# mcu.net
KiCad netlist of a schematic drawn in Altium Designer
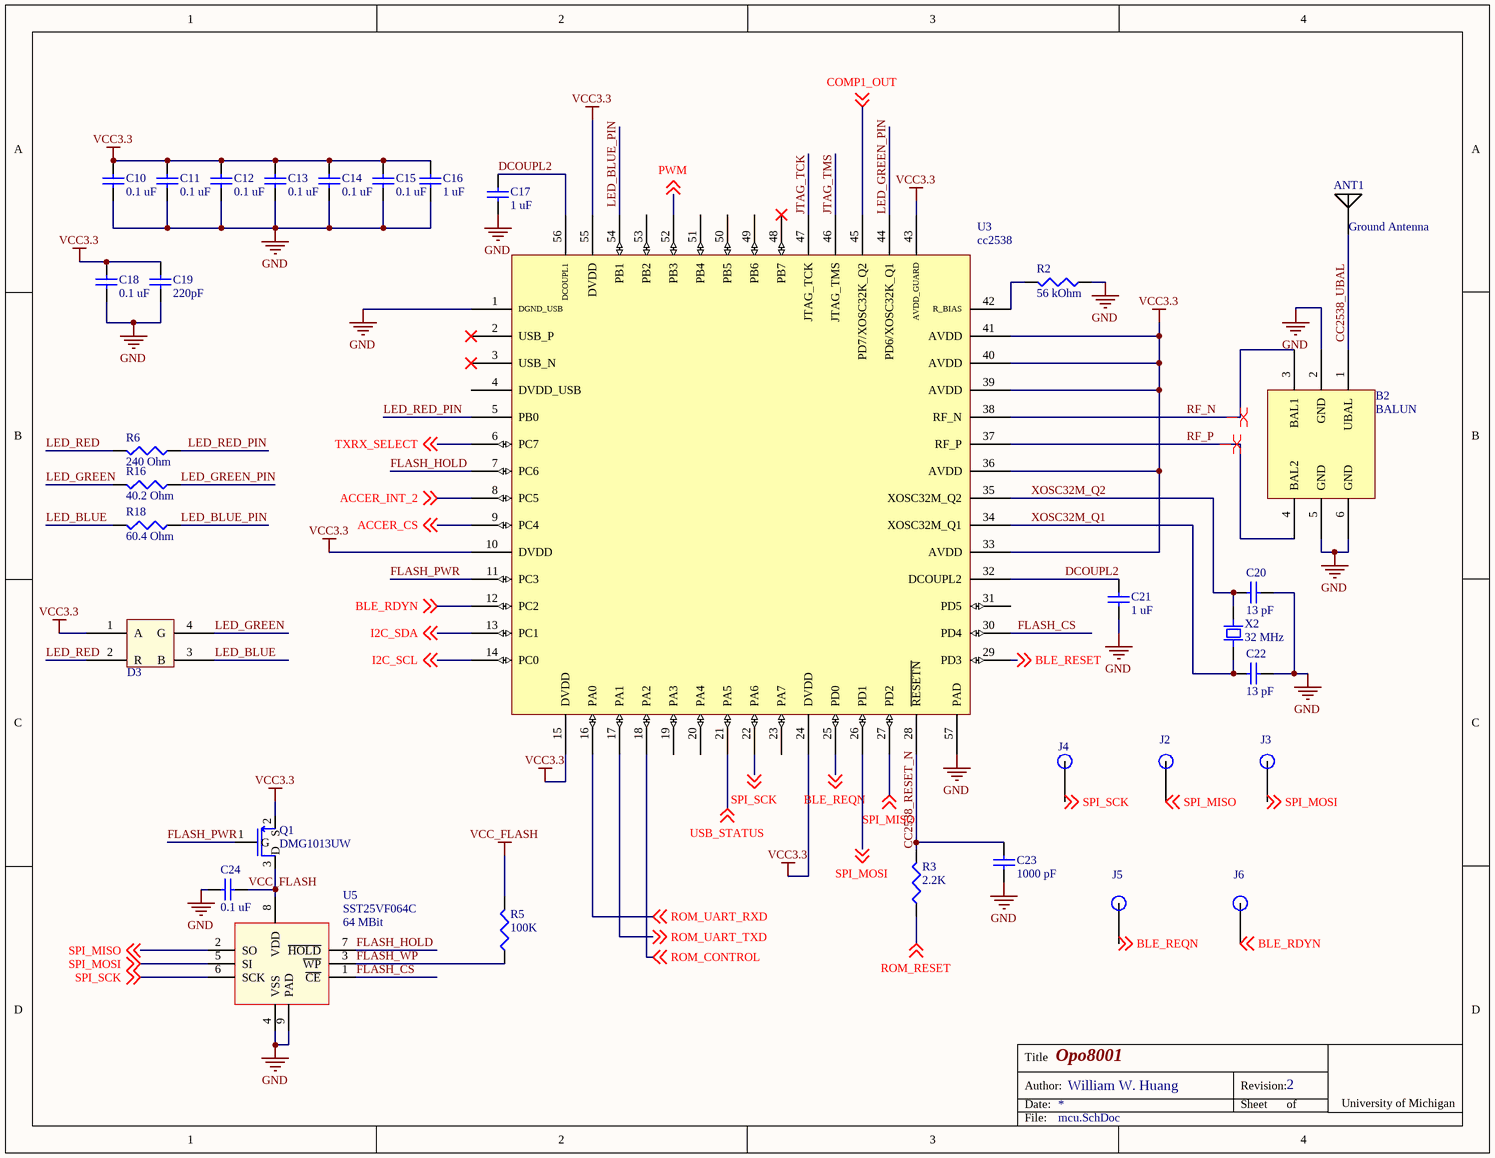
[diagram p0: mcu.SchDoc]

(export (version "E")
  (design (tool "Eeschema 10.0.6"))
  (components
    (comp (ref "ANT1")
      (value "Ground Antenna")
      (footprint "SMD Ground Antenna")
      (description "Molex 2.4 GHz SMD On-Ground Antenna")
      (libsource (lib "opo_general") (part "Molex Antenna"))
    )
    (comp (ref "B2")
      (value "BALUN")
      (footprint "2450BM15A0002")
      (description "Johanson CC253X Balun")
      (fields (field (name "MFR") "Johanson Technology") (field (name "MFR PART NUMBER") "2450BM15A0002"))
      (libsource (lib "opo_general") (part "cc2538_Balun"))
    )
    (comp (ref "C10")
      (value "0.1 uF")
      (footprint "0402")
      (description "Ceramic capacitor, 0.1u, 0402 package")
      (fields (field (name "TOLERANCE") "10%") (field (name "Comment") "Ceramic capacitor"))
      (libsource (lib "rlc") (part "C_0.1u_0402_ceramic"))
    )
    (comp (ref "C11")
      (value "0.1 uF")
      (footprint "0402")
      (description "Ceramic capacitor, 0.1u, 0402 package")
      (fields (field (name "TOLERANCE") "10%") (field (name "Comment") "Ceramic capacitor"))
      (libsource (lib "rlc") (part "C_0.1u_0402_ceramic"))
    )
    (comp (ref "C12")
      (value "0.1 uF")
      (footprint "0402")
      (description "Ceramic capacitor, 0.1u, 0402 package")
      (fields (field (name "TOLERANCE") "10%") (field (name "Comment") "Ceramic capacitor"))
      (libsource (lib "rlc") (part "C_0.1u_0402_ceramic"))
    )
    (comp (ref "C13")
      (value "0.1 uF")
      (footprint "0402")
      (description "Ceramic capacitor, 0.1u, 0402 package")
      (fields (field (name "TOLERANCE") "10%") (field (name "Comment") "Ceramic capacitor"))
      (libsource (lib "rlc") (part "C_0.1u_0402_ceramic"))
    )
    (comp (ref "C14")
      (value "0.1 uF")
      (footprint "0402")
      (description "Ceramic capacitor, 0.1u, 0402 package")
      (fields (field (name "TOLERANCE") "10%") (field (name "Comment") "Ceramic capacitor"))
      (libsource (lib "rlc") (part "C_0.1u_0402_ceramic"))
    )
    (comp (ref "C15")
      (value "0.1 uF")
      (footprint "0402")
      (description "Ceramic capacitor, 0.1u, 0402 package")
      (fields (field (name "TOLERANCE") "10%") (field (name "Comment") "Ceramic capacitor"))
      (libsource (lib "rlc") (part "C_0.1u_0402_ceramic"))
    )
    (comp (ref "C16")
      (value "1 uF")
      (footprint "0402")
      (description "Ceramic capacitor, 1 uF, 0402 package")
      (fields (field (name "TOLERANCE") "10%") (field (name "Comment") "Ceramic capacitor"))
      (libsource (lib "rlc") (part "C_1u_0402_ceramic"))
    )
    (comp (ref "C17")
      (value "1 uF")
      (footprint "0402")
      (description "Ceramic capacitor, 1 uF, 0402 package")
      (fields (field (name "TOLERANCE") "10%") (field (name "Comment") "Ceramic capacitor"))
      (libsource (lib "rlc") (part "C_1u_0402_ceramic"))
    )
    (comp (ref "C18")
      (value "0.1 uF")
      (footprint "0402")
      (description "Ceramic capacitor, 0.1u, 0402 package")
      (fields (field (name "TOLERANCE") "10%") (field (name "Comment") "Ceramic capacitor"))
      (libsource (lib "rlc") (part "C_0.1u_0402_ceramic"))
    )
    (comp (ref "C19")
      (value "220pF")
      (footprint "0402")
      (description "220pF 5% 50 V C0G NP0 0402 ceramic cap")
      (fields (field (name "MFR") "Murata") (field (name "MFR PART NUMBER") "GRM1555C1H221JA01D"))
      (libsource (lib "rlc") (part "C_220pf_0402_ceramic"))
    )
    (comp (ref "C20")
      (value "13 pF")
      (footprint "0402")
      (description "13pf, 50V, 2%, c0G, NP0, 0402, ceramic")
      (fields (field (name "MFR") "Murata") (field (name "MFR PART NUMBER") "GRM1555C1H130GA01D"))
      (libsource (lib "rlc") (part "C_13p_0402"))
    )
    (comp (ref "C21")
      (value "1 uF")
      (footprint "0402")
      (description "Ceramic capacitor, 1 uF, 0402 package")
      (fields (field (name "TOLERANCE") "10%") (field (name "Comment") "Ceramic capacitor"))
      (libsource (lib "rlc") (part "C_1u_0402_ceramic"))
    )
    (comp (ref "C22")
      (value "13 pF")
      (footprint "0402")
      (description "13pf, 50V, 2%, c0G, NP0, 0402, ceramic")
      (fields (field (name "MFR") "Murata") (field (name "MFR PART NUMBER") "GRM1555C1H130GA01D"))
      (libsource (lib "rlc") (part "C_13p_0402"))
    )
    (comp (ref "C23")
      (value "1000 pF")
      (footprint "0402")
      (description "Ceramic capacitor, 1000 pF, 0402 package")
      (fields (field (name "TOLERANCE") "10%") (field (name "Comment") "Ceramic capacitor"))
      (libsource (lib "rlc") (part "C_1000p_0402_ceramic"))
    )
    (comp (ref "C24")
      (value "0.1 uF")
      (footprint "0402")
      (description "Ceramic capacitor, 0.1u, 0402 package")
      (fields (field (name "TOLERANCE") "10%") (field (name "Comment") "Ceramic capacitor"))
      (libsource (lib "rlc") (part "C_0.1u_0402_ceramic"))
    )
    (comp (ref "D3")
      (value "Tri Color LED")
      (footprint "0404")
      (description "LED, RGB, 0404")
      (libsource (lib "rlc") (part "D_LED_RGB_0404"))
    )
    (comp (ref "J2")
      (value "RCU 0603 SMD Testpoint")
      (footprint "RCU_0603")
      (description "0603 SMD Testpoint")
      (libsource (lib "connectors") (part "Testpoint-0603"))
    )
    (comp (ref "J3")
      (value "RCU 0603 SMD Testpoint")
      (footprint "RCU_0603")
      (description "0603 SMD Testpoint")
      (libsource (lib "connectors") (part "Testpoint-0603"))
    )
    (comp (ref "J4")
      (value "RCU 0603 SMD Testpoint")
      (footprint "RCU_0603")
      (description "0603 SMD Testpoint")
      (libsource (lib "connectors") (part "Testpoint-0603"))
    )
    (comp (ref "J5")
      (value "RCU 0603 SMD Testpoint")
      (footprint "RCU_0603")
      (description "0603 SMD Testpoint")
      (libsource (lib "connectors") (part "Testpoint-0603"))
    )
    (comp (ref "J6")
      (value "RCU 0603 SMD Testpoint")
      (footprint "RCU_0603")
      (description "0603 SMD Testpoint")
      (libsource (lib "connectors") (part "Testpoint-0603"))
    )
    (comp (ref "Q1")
      (value "DMG1013UW")
      (footprint "SC70-3")
      (description "P-CHANNEL ENHANCEMENT MODE MOSFET")
      (libsource (lib "opo_general") (part "DMG1013UW"))
    )
    (comp (ref "R2")
      (value "56 kOhm")
      (footprint "0402")
      (description "56 kOhm, 1%, .0603 W, 0402")
      (fields (field (name "MFR") "Rohm") (field (name "MFR PART NUMBER") "MCR01MRTF5602"))
      (libsource (lib "rlc") (part "R_56K_0402"))
    )
    (comp (ref "R3")
      (value "2.2K")
      (footprint "0402")
      (description "Chip resistor, 2.2K, 0402 package")
      (fields (field (name "TOLERANCE") "1%") (field (name "POWER") "1/16 W"))
      (libsource (lib "rlc") (part "R_2.2K_0402"))
    )
    (comp (ref "R5")
      (value "100K")
      (footprint "0402")
      (description "Chip resistor, 100K, 0402 package")
      (fields (field (name "TOLERANCE") "1%") (field (name "POWER") "1/16 W"))
      (libsource (lib "rlc") (part "R_100K_0402"))
    )
    (comp (ref "R6")
      (value "240 Ohm")
      (footprint "0402")
      (description "240 Ohm, 1%, .05W, 0402 Chip Resistor")
      (fields (field (name "Comment") "Chip resistor"))
      (libsource (lib "rlc") (part "R_240_0402"))
    )
    (comp (ref "R16")
      (value "40.2 Ohm")
      (footprint "0402")
      (description "40.2 Ohm 0402 1% Chip Resistor")
      (fields (field (name "Comment") "Chip Resistor"))
      (libsource (lib "rlc") (part "R_40.2_0402"))
    )
    (comp (ref "R18")
      (value "60.4 Ohm")
      (footprint "0402")
      (description "60.4 Ohm, .05W, 1% 0402 Chip Resistor")
      (fields (field (name "Comment") "Chip resistor"))
      (libsource (lib "rlc") (part "R_60.4_0402"))
    )
    (comp (ref "U3")
      (value "cc2538")
      (footprint "QFN50P800X800X100_HS-57N")
      (description "cc2538 MCU/802.15.4 radio")
      (libsource (lib "opo_general") (part "cc2538"))
    )
    (comp (ref "U5")
      (value "SST25VF064C")
      (footprint "WSON")
      (description "64 Mbit SPI Serial Dual I/O Flash")
      (fields (field (name "CAPACITY") "64 MBit"))
      (libsource (lib "opo_general") (part "SST25VF064C"))
    )
    (comp (ref "X2")
      (value "32 MHz")
      (footprint "FA-128")
      (description "32MHz, 10ppm, 10pF, 60 Ohm")
      (fields (field (name "MFR") "Epson") (field (name "MFR PART NUMBER") "FA-128 32.0000MF20X-K3"))
      (libsource (lib "opo_general") (part "X_32M_FA-128"))
    )
  )
  (nets
    (net (code "1") (name "/CC2538_RESET_N") (class "Default")
      (node (ref "C23") (pin "1") (pintype "passive"))
      (node (ref "R3") (pin "1") (pintype "passive"))
      (node (ref "U3") (pin "28") (pinfunction "~{RESETN}_28") (pintype "passive"))
    )
    (net (code "2") (name "/CC2538_UBAL") (class "Default")
      (node (ref "ANT1") (pin "1") (pintype "passive"))
      (node (ref "B2") (pin "1") (pinfunction "UBAL_1") (pintype "passive"))
    )
    (net (code "3") (name "/DCOUPL2") (class "Default")
      (node (ref "C17") (pin "1") (pintype "passive"))
      (node (ref "C21") (pin "1") (pintype "passive"))
      (node (ref "U3") (pin "32") (pinfunction "DCOUPL2_32") (pintype "power_in"))
      (node (ref "U3") (pin "56") (pinfunction "DCOUPL1_56") (pintype "power_in"))
    )
    (net (code "4") (name "/FLASH_CS") (class "Default")
      (node (ref "U3") (pin "30") (pinfunction "PD4_30") (pintype "bidirectional"))
      (node (ref "U5") (pin "1") (pinfunction "~{CE}_1") (pintype "passive"))
    )
    (net (code "5") (name "/FLASH_HOLD") (class "Default")
      (node (ref "U3") (pin "7") (pinfunction "PC6_7") (pintype "bidirectional"))
      (node (ref "U5") (pin "7") (pinfunction "~{HOLD}_7") (pintype "passive"))
    )
    (net (code "6") (name "/FLASH_PWR") (class "Default")
      (node (ref "Q1") (pin "1") (pinfunction "G_1") (pintype "passive"))
      (node (ref "U3") (pin "11") (pinfunction "PC3_11") (pintype "bidirectional"))
    )
    (net (code "7") (name "/FLASH_WP") (class "Default")
      (node (ref "R5") (pin "2") (pintype "passive"))
      (node (ref "U5") (pin "3") (pinfunction "~{WP}_3") (pintype "passive"))
    )
    (net (code "8") (name "/JTAG_TCK") (class "Default")
      (node (ref "U3") (pin "47") (pinfunction "JTAG_TCK_47") (pintype "passive"))
    )
    (net (code "9") (name "/JTAG_TMS") (class "Default")
      (node (ref "U3") (pin "46") (pinfunction "JTAG_TMS_46") (pintype "passive"))
    )
    (net (code "10") (name "/LED_BLUE") (class "Default")
      (node (ref "D3") (pin "3") (pinfunction "B_3") (pintype "passive"))
      (node (ref "R18") (pin "1") (pintype "passive"))
    )
    (net (code "11") (name "/LED_BLUE_PIN") (class "Default")
      (node (ref "R18") (pin "2") (pintype "passive"))
      (node (ref "U3") (pin "54") (pinfunction "PB1_54") (pintype "bidirectional"))
    )
    (net (code "12") (name "/LED_GREEN") (class "Default")
      (node (ref "D3") (pin "4") (pinfunction "G_4") (pintype "passive"))
      (node (ref "R16") (pin "1") (pintype "passive"))
    )
    (net (code "13") (name "/LED_GREEN_PIN") (class "Default")
      (node (ref "R16") (pin "2") (pintype "passive"))
      (node (ref "U3") (pin "44") (pinfunction "PD6/XOSC32K_Q1_44") (pintype "passive"))
    )
    (net (code "14") (name "/LED_RED") (class "Default")
      (node (ref "D3") (pin "2") (pinfunction "R_2") (pintype "passive"))
      (node (ref "R6") (pin "1") (pintype "passive"))
    )
    (net (code "15") (name "/LED_RED_PIN") (class "Default")
      (node (ref "R6") (pin "2") (pintype "passive"))
      (node (ref "U3") (pin "5") (pinfunction "PB0_5") (pintype "passive"))
    )
    (net (code "16") (name "/RF_N") (class "Default")
      (node (ref "B2") (pin "3") (pinfunction "BAL1_3") (pintype "passive"))
      (node (ref "U3") (pin "38") (pinfunction "RF_N_38") (pintype "passive"))
    )
    (net (code "17") (name "/RF_P") (class "Default")
      (node (ref "B2") (pin "4") (pinfunction "BAL2_4") (pintype "passive"))
      (node (ref "U3") (pin "37") (pinfunction "RF_P_37") (pintype "passive"))
    )
    (net (code "18") (name "/XOSC32M_Q1") (class "Default")
      (node (ref "C22") (pin "2") (pintype "passive"))
      (node (ref "U3") (pin "34") (pinfunction "XOSC32M_Q1_34") (pintype "passive"))
      (node (ref "X2") (pin "3") (pintype "passive"))
    )
    (net (code "19") (name "/XOSC32M_Q2") (class "Default")
      (node (ref "C20") (pin "1") (pintype "passive"))
      (node (ref "U3") (pin "35") (pinfunction "XOSC32M_Q2_35") (pintype "passive"))
      (node (ref "X2") (pin "1") (pintype "passive"))
    )
    (net (code "20") (name "ACCER_CS") (class "Default")
      (node (ref "U3") (pin "9") (pinfunction "PC4_9") (pintype "bidirectional"))
    )
    (net (code "21") (name "ACCER_INT_2") (class "Default")
      (node (ref "U3") (pin "8") (pinfunction "PC5_8") (pintype "bidirectional"))
    )
    (net (code "22") (name "BLE_RDYN") (class "Default")
      (node (ref "J6") (pin "1") (pinfunction "J_1") (pintype "passive"))
      (node (ref "U3") (pin "12") (pinfunction "PC2_12") (pintype "bidirectional"))
    )
    (net (code "23") (name "BLE_REQN") (class "Default")
      (node (ref "J5") (pin "1") (pinfunction "J_1") (pintype "passive"))
      (node (ref "U3") (pin "25") (pinfunction "PD0_25") (pintype "bidirectional"))
    )
    (net (code "24") (name "BLE_RESET") (class "Default")
      (node (ref "U3") (pin "29") (pinfunction "PD3_29") (pintype "bidirectional"))
    )
    (net (code "25") (name "COMP1_OUT") (class "Default")
      (node (ref "U3") (pin "45") (pinfunction "PD7/XOSC32K_Q2_45") (pintype "passive"))
    )
    (net (code "26") (name "GND") (class "Default")
      (node (ref "B2") (pin "2") (pinfunction "GND_2") (pintype "passive"))
      (node (ref "B2") (pin "5") (pinfunction "GND_5") (pintype "passive"))
      (node (ref "B2") (pin "6") (pinfunction "GND_6") (pintype "passive"))
      (node (ref "C10") (pin "2") (pintype "passive"))
      (node (ref "C11") (pin "2") (pintype "passive"))
      (node (ref "C12") (pin "2") (pintype "passive"))
      (node (ref "C13") (pin "2") (pintype "passive"))
      (node (ref "C14") (pin "2") (pintype "passive"))
      (node (ref "C15") (pin "2") (pintype "passive"))
      (node (ref "C16") (pin "2") (pintype "passive"))
      (node (ref "C17") (pin "2") (pintype "passive"))
      (node (ref "C18") (pin "2") (pintype "passive"))
      (node (ref "C19") (pin "2") (pintype "passive"))
      (node (ref "C20") (pin "2") (pintype "passive"))
      (node (ref "C21") (pin "2") (pintype "passive"))
      (node (ref "C22") (pin "1") (pintype "passive"))
      (node (ref "C23") (pin "2") (pintype "passive"))
      (node (ref "C24") (pin "1") (pintype "passive"))
      (node (ref "R2") (pin "2") (pintype "passive"))
      (node (ref "U3") (pin "1") (pinfunction "DGND_USB_1") (pintype "passive"))
      (node (ref "U3") (pin "57") (pinfunction "PAD_57") (pintype "passive"))
      (node (ref "U5") (pin "4") (pinfunction "VSS_4") (pintype "passive"))
      (node (ref "U5") (pin "9") (pinfunction "PAD_9") (pintype "passive"))
    )
    (net (code "27") (name "I2C_SCL") (class "Default")
      (node (ref "U3") (pin "14") (pinfunction "PC0_14") (pintype "bidirectional"))
    )
    (net (code "28") (name "I2C_SDA") (class "Default")
      (node (ref "U3") (pin "13") (pinfunction "PC1_13") (pintype "bidirectional"))
    )
    (net (code "29") (name "Net-(U3-R_BIAS)") (class "Default")
      (node (ref "R2") (pin "1") (pintype "passive"))
      (node (ref "U3") (pin "42") (pinfunction "R_BIAS_42") (pintype "passive"))
    )
    (net (code "30") (name "PWM") (class "Default")
      (node (ref "U3") (pin "52") (pinfunction "PB3_52") (pintype "bidirectional"))
    )
    (net (code "31") (name "ROM_CONTROL") (class "Default")
      (node (ref "U3") (pin "18") (pinfunction "PA2_18") (pintype "bidirectional"))
    )
    (net (code "32") (name "ROM_RESET") (class "Default") (node (ref "R3") (pin "2") (pintype "passive")))
    (net (code "33") (name "ROM_UART_RXD") (class "Default")
      (node (ref "U3") (pin "16") (pinfunction "PA0_16") (pintype "bidirectional"))
    )
    (net (code "34") (name "ROM_UART_TXD") (class "Default")
      (node (ref "U3") (pin "17") (pinfunction "PA1_17") (pintype "bidirectional"))
    )
    (net (code "35") (name "SPI_MISO") (class "Default")
      (node (ref "J2") (pin "1") (pinfunction "J_1") (pintype "passive"))
      (node (ref "U3") (pin "27") (pinfunction "PD2_27") (pintype "bidirectional"))
      (node (ref "U5") (pin "2") (pinfunction "SO_2") (pintype "passive"))
    )
    (net (code "36") (name "SPI_MOSI") (class "Default")
      (node (ref "J3") (pin "1") (pinfunction "J_1") (pintype "passive"))
      (node (ref "U3") (pin "26") (pinfunction "PD1_26") (pintype "bidirectional"))
      (node (ref "U5") (pin "5") (pinfunction "SI_5") (pintype "passive"))
    )
    (net (code "37") (name "SPI_SCK") (class "Default")
      (node (ref "J4") (pin "1") (pinfunction "J_1") (pintype "passive"))
      (node (ref "U3") (pin "22") (pinfunction "PA6_22") (pintype "bidirectional"))
      (node (ref "U5") (pin "6") (pinfunction "SCK_6") (pintype "passive"))
    )
    (net (code "38") (name "TXRX_SELECT") (class "Default")
      (node (ref "U3") (pin "6") (pinfunction "PC7_6") (pintype "bidirectional"))
    )
    (net (code "39") (name "USB_STATUS") (class "Default")
      (node (ref "U3") (pin "21") (pinfunction "PA5_21") (pintype "bidirectional"))
    )
    (net (code "40") (name "VCC3.3") (class "Default")
      (node (ref "C10") (pin "1") (pintype "passive"))
      (node (ref "C11") (pin "1") (pintype "passive"))
      (node (ref "C12") (pin "1") (pintype "passive"))
      (node (ref "C13") (pin "1") (pintype "passive"))
      (node (ref "C14") (pin "1") (pintype "passive"))
      (node (ref "C15") (pin "1") (pintype "passive"))
      (node (ref "C16") (pin "1") (pintype "passive"))
      (node (ref "C18") (pin "1") (pintype "passive"))
      (node (ref "C19") (pin "1") (pintype "passive"))
      (node (ref "D3") (pin "1") (pinfunction "A_1") (pintype "passive"))
      (node (ref "Q1") (pin "2") (pinfunction "S_2") (pintype "passive"))
      (node (ref "U3") (pin "10") (pinfunction "DVDD_10") (pintype "power_in"))
      (node (ref "U3") (pin "15") (pinfunction "DVDD_15") (pintype "power_in"))
      (node (ref "U3") (pin "24") (pinfunction "DVDD_24") (pintype "power_in"))
      (node (ref "U3") (pin "33") (pinfunction "AVDD_33") (pintype "power_in"))
      (node (ref "U3") (pin "36") (pinfunction "AVDD_36") (pintype "power_in"))
      (node (ref "U3") (pin "39") (pinfunction "AVDD_39") (pintype "power_in"))
      (node (ref "U3") (pin "40") (pinfunction "AVDD_40") (pintype "power_in"))
      (node (ref "U3") (pin "41") (pinfunction "AVDD_41") (pintype "power_in"))
      (node (ref "U3") (pin "43") (pinfunction "AVDD_GUARD_43") (pintype "power_in"))
      (node (ref "U3") (pin "55") (pinfunction "DVDD_55") (pintype "power_in"))
    )
    (net (code "41") (name "VCC_FLASH") (class "Default")
      (node (ref "C24") (pin "2") (pintype "passive"))
      (node (ref "Q1") (pin "3") (pinfunction "D_3") (pintype "passive"))
      (node (ref "R5") (pin "1") (pintype "passive"))
      (node (ref "U5") (pin "8") (pinfunction "VDD_8") (pintype "passive"))
    )
    (net (code "42") (name "unconnected-(U3-DVDD_USB-Pad4)") (class "Default")
      (node (ref "U3") (pin "4") (pinfunction "DVDD_USB_4") (pintype "passive"))
    )
    (net (code "43") (name "unconnected-(U3-PA3-Pad19)") (class "Default")
      (node (ref "U3") (pin "19") (pinfunction "PA3_19") (pintype "bidirectional"))
    )
    (net (code "44") (name "unconnected-(U3-PA4-Pad20)") (class "Default")
      (node (ref "U3") (pin "20") (pinfunction "PA4_20") (pintype "bidirectional"))
    )
    (net (code "45") (name "unconnected-(U3-PA7-Pad23)") (class "Default")
      (node (ref "U3") (pin "23") (pinfunction "PA7_23") (pintype "bidirectional"))
    )
    (net (code "46") (name "unconnected-(U3-PB2-Pad53)") (class "Default")
      (node (ref "U3") (pin "53") (pinfunction "PB2_53") (pintype "bidirectional"))
    )
    (net (code "47") (name "unconnected-(U3-PB4-Pad51)") (class "Default")
      (node (ref "U3") (pin "51") (pinfunction "PB4_51") (pintype "bidirectional"))
    )
    (net (code "48") (name "unconnected-(U3-PB5-Pad50)") (class "Default")
      (node (ref "U3") (pin "50") (pinfunction "PB5_50") (pintype "bidirectional"))
    )
    (net (code "49") (name "unconnected-(U3-PB6-Pad49)") (class "Default")
      (node (ref "U3") (pin "49") (pinfunction "PB6_49") (pintype "bidirectional"))
    )
    (net (code "50") (name "unconnected-(U3-PB7-Pad48)") (class "Default")
      (node (ref "U3") (pin "48") (pinfunction "PB7_48") (pintype "bidirectional+no_connect"))
    )
    (net (code "51") (name "unconnected-(U3-PD5-Pad31)") (class "Default")
      (node (ref "U3") (pin "31") (pinfunction "PD5_31") (pintype "bidirectional"))
    )
    (net (code "52") (name "unconnected-(U3-USB_N-Pad3)") (class "Default")
      (node (ref "U3") (pin "3") (pinfunction "USB_N_3") (pintype "passive+no_connect"))
    )
    (net (code "53") (name "unconnected-(U3-USB_P-Pad2)") (class "Default")
      (node (ref "U3") (pin "2") (pinfunction "USB_P_2") (pintype "passive+no_connect"))
    )
  )
)
